# SoM.net
KiCad netlist of a schematic drawn in Altium Designer
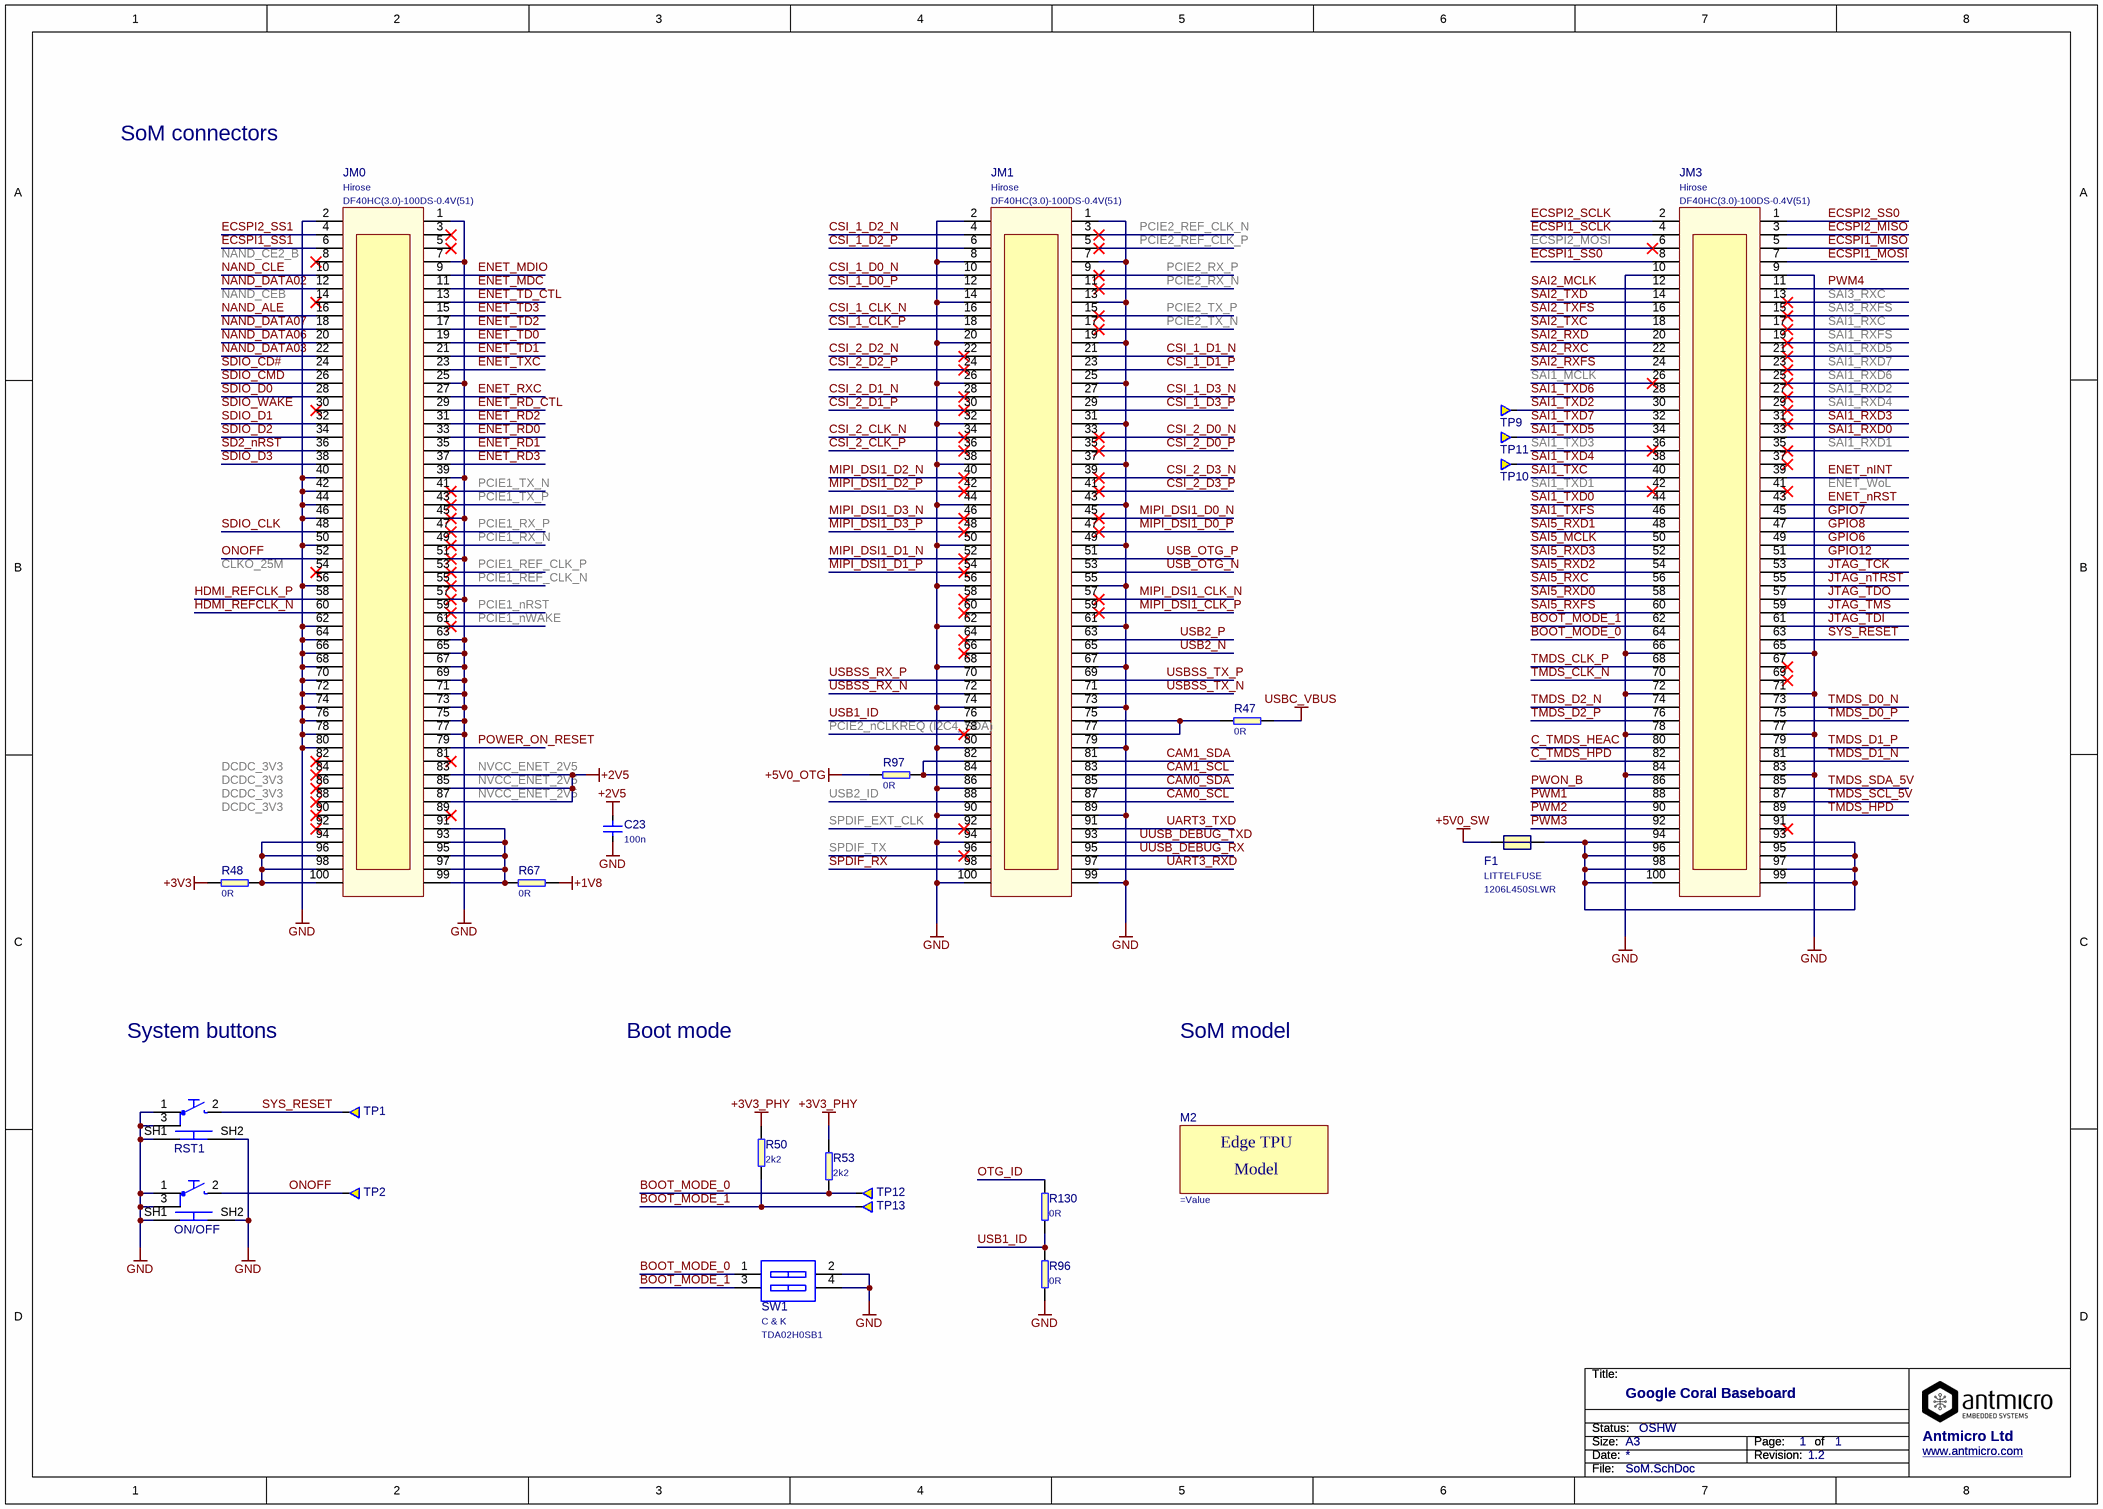
[diagram p0: SoM.SchDoc]

(export (version "E")
  (design (tool "Eeschema 10.0.6"))
  (components
    (comp (ref "C23")
      (value "100n")
      (footprint "C_0402")
      (description "MLCC SMT Capacitor 100nF 0402")
      (fields (field (name "PARTNUMBER") "C_100n_0402"))
      (libsource (lib "altium-import") (part "root_3_C_"))
    )
    (comp (ref "F1")
      (value "Value")
      (footprint "Fuse-1206")
      (description "PTC RESET 6V LO RHO 1206 4.50A")
      (fields (field (name "PARTNUMBER") "1206L450SLWR") (field (name "MANUFACTURER") "LITTELFUSE"))
      (libsource (lib "altium-import") (part "root_0_Fuse_"))
    )
    (comp (ref "JM0")
      (value "DF40HC(3.0)-100DS-0.4V(51)")
      (footprint "DF40HC(3.0)-100DS-0.4V(51)")
      (description "CONN RCPT 100POS 0.4MM SMD GOLD")
      (fields (field (name "MANUFACTURER") "Hirose"))
      (libsource (lib "altium-import") (part "root_0_DF40HC(3.0)-100DS-0.4V(51)_"))
    )
    (comp (ref "JM1")
      (value "DF40HC(3.0)-100DS-0.4V(51)")
      (footprint "DF40HC(3.0)-100DS-0.4V(51)")
      (description "CONN RCPT 100POS 0.4MM SMD GOLD")
      (fields (field (name "MANUFACTURER") "Hirose"))
      (libsource (lib "altium-import") (part "root_0_DF40HC(3.0)-100DS-0.4V(51)_"))
    )
    (comp (ref "JM3")
      (value "DF40HC(3.0)-100DS-0.4V(51)")
      (footprint "DF40HC(3.0)-100DS-0.4V(51)")
      (description "CONN RCPT 100POS 0.4MM SMD GOLD")
      (fields (field (name "MANUFACTURER") "Hirose"))
      (libsource (lib "altium-import") (part "root_0_DF40HC(3.0)-100DS-0.4V(51)_"))
    )
    (comp (ref "M2")
      (value "~")
      (footprint "Edge-TPU-SOM-model")
      (description "Edge TPU SOM")
      (fields (field (name "PARTNUMBER") "Edge-TPU-SOM-model"))
      (libsource (lib "altium-import") (part "root_0_Edge-TPU-Module-model_"))
    )
    (comp (ref "ON/OFF")
      (value "TL3340AF160QG")
      (footprint "TL3340AF160QG")
      (description "E-SWITCH  TL3340AF160QG  SWITCH, TACTILE SPST 50mA, SMD GULL WING")
      (fields (field (name "MANUFACTURER") "E-SWITCH"))
      (libsource (lib "altium-import") (part "root_0_TL3340AF160QG_"))
    )
    (comp (ref "R47")
      (value "0R")
      (footprint "0402")
      (description "SMT Resistor 0402")
      (fields (field (name "PARTNUMBER") "R_0R_0402"))
      (libsource (lib "altium-import") (part "root_2_R_"))
    )
    (comp (ref "R48")
      (value "0R")
      (footprint "0805")
      (description "SMT Resistor 0R 0805")
      (fields (field (name "PARTNUMBER") "R_0R_0805"))
      (libsource (lib "altium-import") (part "root_2_R_"))
    )
    (comp (ref "R50")
      (value "2k2")
      (footprint "0402")
      (description "RES, 2k2, 0402, 5%")
      (fields (field (name "PARTNUMBER") "R_2k2_0402"))
      (libsource (lib "altium-import") (part "root_1_R_"))
    )
    (comp (ref "R53")
      (value "2k2")
      (footprint "0402")
      (description "RES, 2k2, 0402, 5%")
      (fields (field (name "PARTNUMBER") "R_2k2_0402"))
      (libsource (lib "altium-import") (part "root_1_R_"))
    )
    (comp (ref "R67")
      (value "0R")
      (footprint "0805")
      (description "SMT Resistor 0R 0805")
      (fields (field (name "PARTNUMBER") "R_0R_0805"))
      (libsource (lib "altium-import") (part "root_0_R_"))
    )
    (comp (ref "R96")
      (value "0R")
      (footprint "0402")
      (description "SMT Resistor 0402")
      (fields (field (name "PARTNUMBER") "R_0R_0402"))
      (libsource (lib "altium-import") (part "root_1_R_"))
    )
    (comp (ref "R97")
      (value "0R")
      (footprint "0402")
      (description "SMT Resistor 0402")
      (fields (field (name "PARTNUMBER") "R_0R_0402"))
      (libsource (lib "altium-import") (part "root_2_R_"))
    )
    (comp (ref "R130")
      (value "0R")
      (footprint "0402")
      (description "SMT Resistor 0402")
      (fields (field (name "PARTNUMBER") "R_0R_0402"))
      (libsource (lib "altium-import") (part "root_1_R_"))
    )
    (comp (ref "RST1")
      (value "TL3340AF160QG")
      (footprint "TL3340AF160QG")
      (description "E-SWITCH  TL3340AF160QG  SWITCH, TACTILE SPST 50mA, SMD GULL WING")
      (fields (field (name "MANUFACTURER") "E-SWITCH"))
      (libsource (lib "altium-import") (part "root_0_TL3340AF160QG_"))
    )
    (comp (ref "SW1")
      (value "TDA02H0SB1")
      (footprint "TDA02H0SB1")
      (description "TDA02H0SB1 - DIP / SIP Switch, 2 Circuits, SPST, SMD, TDA Series, DIP, 24 V")
      (fields (field (name "MANUFACTURER") "C & K"))
      (libsource (lib "altium-import") (part "root_0_TDA02H0SB1_"))
    )
    (comp (ref "TP1")
      (value "Testpad")
      (footprint "TP-R-1.5")
      (description "Testpad, round, 1.5mm")
      (libsource (lib "altium-import") (part "root_3_Testpad_"))
    )
    (comp (ref "TP2")
      (value "Testpad")
      (footprint "TP-R-1.5")
      (description "Testpad, round, 1.5mm")
      (libsource (lib "altium-import") (part "root_3_Testpad_"))
    )
    (comp (ref "TP9")
      (value "Testpad")
      (footprint "TP-R-1.5")
      (description "Testpad, round, 1.5mm")
      (libsource (lib "altium-import") (part "root_1_Testpad_"))
    )
    (comp (ref "TP10")
      (value "Testpad")
      (footprint "TP-R-1.5")
      (description "Testpad, round, 1.5mm")
      (libsource (lib "altium-import") (part "root_1_Testpad_"))
    )
    (comp (ref "TP11")
      (value "Testpad")
      (footprint "TP-R-1.5")
      (description "Testpad, round, 1.5mm")
      (libsource (lib "altium-import") (part "root_1_Testpad_"))
    )
    (comp (ref "TP12")
      (value "Testpad")
      (footprint "TP-R-1.5")
      (description "Testpad, round, 1.5mm")
      (libsource (lib "altium-import") (part "root_3_Testpad_"))
    )
    (comp (ref "TP13")
      (value "Testpad")
      (footprint "TP-R-1.5")
      (description "Testpad, round, 1.5mm")
      (libsource (lib "altium-import") (part "root_3_Testpad_"))
    )
  )
  (nets
    (net (code "1") (name "+1V8") (class "Default") (node (ref "R67") (pin "2") (pintype "passive")))
    (net (code "2") (name "+2V5") (class "Default")
      (node (ref "C23") (pin "1") (pinfunction "1_1") (pintype "passive"))
      (node (ref "JM0") (pin "83") (pinfunction "PB8_83") (pintype "passive"))
      (node (ref "JM0") (pin "85") (pinfunction "PB8_85") (pintype "passive"))
      (node (ref "JM0") (pin "87") (pinfunction "PB8_87") (pintype "passive"))
    )
    (net (code "3") (name "+3V3") (class "Default") (node (ref "R48") (pin "2") (pintype "passive")))
    (net (code "4") (name "+3V3_PHY") (class "Default")
      (node (ref "R50") (pin "2") (pintype "passive"))
      (node (ref "R53") (pin "2") (pintype "passive"))
    )
    (net (code "5") (name "+5V0_OTG") (class "Default") (node (ref "R97") (pin "2") (pintype "passive")))
    (net (code "6") (name "+5V0_SW") (class "Default")
      (node (ref "F1") (pin "1") (pinfunction "1_1") (pintype "passive"))
    )
    (net (code "7") (name "/BOOT_MODE_0") (class "Default")
      (node (ref "JM3") (pin "64") (pinfunction "GND_64") (pintype "passive"))
      (node (ref "R53") (pin "1") (pintype "passive"))
      (node (ref "SW1") (pin "1") (pinfunction "1_1") (pintype "passive"))
      (node (ref "TP12") (pin "1") (pintype "passive"))
    )
    (net (code "8") (name "/BOOT_MODE_1") (class "Default")
      (node (ref "JM3") (pin "62") (pinfunction "PB12_62") (pintype "passive"))
      (node (ref "R50") (pin "1") (pintype "passive"))
      (node (ref "SW1") (pin "3") (pinfunction "3_3") (pintype "passive"))
      (node (ref "TP13") (pin "1") (pintype "passive"))
    )
    (net (code "9") (name "/CAM0_SCL") (class "Default")
      (node (ref "JM1") (pin "87") (pinfunction "PB8_87") (pintype "passive"))
    )
    (net (code "10") (name "/CAM0_SDA") (class "Default")
      (node (ref "JM1") (pin "85") (pinfunction "PB8_85") (pintype "passive"))
    )
    (net (code "11") (name "/CAM1_SCL") (class "Default")
      (node (ref "JM1") (pin "83") (pinfunction "PB8_83") (pintype "passive"))
    )
    (net (code "12") (name "/CAM1_SDA") (class "Default")
      (node (ref "JM1") (pin "81") (pinfunction "PB8_81") (pintype "passive"))
    )
    (net (code "14") (name "/CSI_1_CLK_N") (class "Default")
      (node (ref "JM1") (pin "16") (pinfunction "PE10_16") (pintype "passive"))
    )
    (net (code "15") (name "/CSI_1_CLK_P") (class "Default")
      (node (ref "JM1") (pin "18") (pinfunction "PE9_18") (pintype "passive"))
    )
    (net (code "16") (name "/CSI_1_D0_N") (class "Default")
      (node (ref "JM1") (pin "10") (pinfunction "PB15_10") (pintype "passive"))
    )
    (net (code "17") (name "/CSI_1_D0_P") (class "Default")
      (node (ref "JM1") (pin "12") (pinfunction "PB14_12") (pintype "passive"))
    )
    (net (code "18") (name "/CSI_1_D1_N") (class "Default")
      (node (ref "JM1") (pin "21") (pinfunction "1V8_21") (pintype "passive"))
    )
    (net (code "19") (name "/CSI_1_D1_P") (class "Default")
      (node (ref "JM1") (pin "23") (pinfunction "PE7_23") (pintype "passive"))
    )
    (net (code "20") (name "/CSI_1_D2_N") (class "Default")
      (node (ref "JM1") (pin "4") (pinfunction "2_4") (pintype "passive"))
    )
    (net (code "21") (name "/CSI_1_D2_P") (class "Default")
      (node (ref "JM1") (pin "6") (pinfunction "3_6") (pintype "passive"))
    )
    (net (code "22") (name "/CSI_1_D3_N") (class "Default")
      (node (ref "JM1") (pin "27") (pinfunction "PD1_27") (pintype "passive"))
    )
    (net (code "23") (name "/CSI_1_D3_P") (class "Default")
      (node (ref "JM1") (pin "29") (pinfunction "PD0_29") (pintype "passive"))
    )
    (net (code "24") (name "/CSI_2_CLK_N") (class "Default")
      (node (ref "JM1") (pin "34") (pinfunction "PC10_34") (pintype "passive+no_connect"))
    )
    (net (code "25") (name "/CSI_2_CLK_P") (class "Default")
      (node (ref "JM1") (pin "36") (pinfunction "PA15_36") (pintype "passive+no_connect"))
    )
    (net (code "26") (name "/CSI_2_D0_N") (class "Default")
      (node (ref "JM1") (pin "33") (pinfunction "PD4_33") (pintype "passive+no_connect"))
    )
    (net (code "27") (name "/CSI_2_D0_P") (class "Default")
      (node (ref "JM1") (pin "35") (pinfunction "PD7_35") (pintype "passive+no_connect"))
    )
    (net (code "28") (name "/CSI_2_D1_N") (class "Default")
      (node (ref "JM1") (pin "28") (pinfunction "GND_28") (pintype "passive+no_connect"))
    )
    (net (code "29") (name "/CSI_2_D1_P") (class "Default")
      (node (ref "JM1") (pin "30") (pinfunction "PA9_30") (pintype "passive+no_connect"))
    )
    (net (code "30") (name "/CSI_2_D2_N") (class "Default")
      (node (ref "JM1") (pin "22") (pinfunction "PD15_22") (pintype "passive+no_connect"))
    )
    (net (code "31") (name "/CSI_2_D2_P") (class "Default")
      (node (ref "JM1") (pin "24") (pinfunction "PC6_24") (pintype "passive+no_connect"))
    )
    (net (code "32") (name "/CSI_2_D3_N") (class "Default")
      (node (ref "JM1") (pin "39") (pinfunction "GND_39") (pintype "passive+no_connect"))
    )
    (net (code "33") (name "/CSI_2_D3_P") (class "Default")
      (node (ref "JM1") (pin "41") (pinfunction "RST_JTAG_O_41") (pintype "passive+no_connect"))
    )
    (net (code "34") (name "/C_TMDS_HEAC") (class "Default")
      (node (ref "JM3") (pin "80") (pinfunction "ETH_R_N_80") (pintype "passive"))
    )
    (net (code "35") (name "/C_TMDS_HPD") (class "Default")
      (node (ref "JM3") (pin "82") (pinfunction "PB8_82") (pintype "passive"))
    )
    (net (code "37") (name "/ECSPI1_MISO") (class "Default")
      (node (ref "JM3") (pin "5") (pinfunction "ETH_T_P_5") (pintype "passive"))
    )
    (net (code "38") (name "/ECSPI1_MOSI") (class "Default")
      (node (ref "JM3") (pin "7") (pinfunction "ETH_L1_C_7") (pintype "passive"))
    )
    (net (code "39") (name "/ECSPI1_SCLK") (class "Default")
      (node (ref "JM3") (pin "4") (pinfunction "2_4") (pintype "passive"))
    )
    (net (code "40") (name "/ECSPI1_SS0") (class "Default")
      (node (ref "JM3") (pin "8") (pinfunction "GND_8") (pintype "passive"))
    )
    (net (code "41") (name "/ECSPI1_SS1") (class "Default")
      (node (ref "JM0") (pin "6") (pinfunction "3_6") (pintype "passive"))
    )
    (net (code "42") (name "/ECSPI2_MISO") (class "Default")
      (node (ref "JM3") (pin "3") (pinfunction "ETH_T_N_3") (pintype "passive"))
    )
    (net (code "43") (name "/ECSPI2_MOSI") (class "Default")
      (node (ref "JM3") (pin "6") (pinfunction "3_6") (pintype "passive+no_connect"))
    )
    (net (code "44") (name "/ECSPI2_SCLK") (class "Default")
      (node (ref "JM3") (pin "2") (pinfunction "1_2") (pintype "passive"))
    )
    (net (code "45") (name "/ECSPI2_SS0") (class "Default")
      (node (ref "JM3") (pin "1") (pinfunction "ETH_VDD_1") (pintype "passive"))
    )
    (net (code "46") (name "/ECSPI2_SS1") (class "Default")
      (node (ref "JM0") (pin "4") (pinfunction "2_4") (pintype "passive"))
    )
    (net (code "47") (name "/ENET_MDC") (class "Default")
      (node (ref "JM0") (pin "11") (pinfunction "BATT_P_11") (pintype "passive"))
    )
    (net (code "48") (name "/ENET_MDIO") (class "Default")
      (node (ref "JM0") (pin "9") (pinfunction "GND_9") (pintype "passive"))
    )
    (net (code "49") (name "/ENET_RD0") (class "Default")
      (node (ref "JM0") (pin "33") (pinfunction "PD4_33") (pintype "passive"))
    )
    (net (code "50") (name "/ENET_RD1") (class "Default")
      (node (ref "JM0") (pin "35") (pinfunction "PD7_35") (pintype "passive"))
    )
    (net (code "51") (name "/ENET_RD2") (class "Default")
      (node (ref "JM0") (pin "31") (pinfunction "PD5_31") (pintype "passive"))
    )
    (net (code "52") (name "/ENET_RD3") (class "Default")
      (node (ref "JM0") (pin "37") (pinfunction "PF0_37") (pintype "passive"))
    )
    (net (code "53") (name "/ENET_RD_CTL") (class "Default")
      (node (ref "JM0") (pin "29") (pinfunction "PD0_29") (pintype "passive"))
    )
    (net (code "54") (name "/ENET_RXC") (class "Default")
      (node (ref "JM0") (pin "27") (pinfunction "PD1_27") (pintype "passive"))
    )
    (net (code "55") (name "/ENET_TD0") (class "Default")
      (node (ref "JM0") (pin "19") (pinfunction "CHRG_NTC_19") (pintype "passive"))
    )
    (net (code "56") (name "/ENET_TD1") (class "Default")
      (node (ref "JM0") (pin "21") (pinfunction "1V8_21") (pintype "passive"))
    )
    (net (code "57") (name "/ENET_TD2") (class "Default")
      (node (ref "JM0") (pin "17") (pinfunction "USB_VBUS_17") (pintype "passive"))
    )
    (net (code "58") (name "/ENET_TD3") (class "Default")
      (node (ref "JM0") (pin "15") (pinfunction "USB_VBUS_15") (pintype "passive"))
    )
    (net (code "59") (name "/ENET_TD_CTL") (class "Default")
      (node (ref "JM0") (pin "13") (pinfunction "BATT_P_13") (pintype "passive"))
    )
    (net (code "60") (name "/ENET_TXC") (class "Default")
      (node (ref "JM0") (pin "23") (pinfunction "PE7_23") (pintype "passive"))
    )
    (net (code "62") (name "/ENET_nINT") (class "Default")
      (node (ref "JM3") (pin "39") (pinfunction "GND_39") (pintype "passive"))
    )
    (net (code "63") (name "/ENET_nRST") (class "Default")
      (node (ref "JM3") (pin "43") (pinfunction "PB3_43") (pintype "passive"))
    )
    (net (code "64") (name "/GPIO6") (class "Default")
      (node (ref "JM3") (pin "49") (pinfunction "PI2_49") (pintype "passive"))
    )
    (net (code "65") (name "/GPIO7") (class "Default")
      (node (ref "JM3") (pin "45") (pinfunction "PA14_45") (pintype "passive"))
    )
    (net (code "66") (name "/GPIO8") (class "Default")
      (node (ref "JM3") (pin "47") (pinfunction "PA13_47") (pintype "passive"))
    )
    (net (code "67") (name "/GPIO12") (class "Default")
      (node (ref "JM3") (pin "51") (pinfunction "PI3_51") (pintype "passive"))
    )
    (net (code "68") (name "/HDMI_REFCLK_N") (class "Default")
      (node (ref "JM0") (pin "60") (pinfunction "PI1_60") (pintype "passive"))
    )
    (net (code "69") (name "/HDMI_REFCLK_P") (class "Default")
      (node (ref "JM0") (pin "58") (pinfunction "PB5_58") (pintype "passive"))
    )
    (net (code "70") (name "/JTAG_TCK") (class "Default")
      (node (ref "JM3") (pin "53") (pinfunction "PA12_53") (pintype "passive"))
    )
    (net (code "71") (name "/JTAG_TDI") (class "Default")
      (node (ref "JM3") (pin "61") (pinfunction "PC7_61") (pintype "passive"))
    )
    (net (code "72") (name "/JTAG_TDO") (class "Default")
      (node (ref "JM3") (pin "57") (pinfunction "PI0_57") (pintype "passive"))
    )
    (net (code "73") (name "/JTAG_TMS") (class "Default")
      (node (ref "JM3") (pin "59") (pinfunction "PD6_59") (pintype "passive"))
    )
    (net (code "74") (name "/JTAG_nTRST") (class "Default")
      (node (ref "JM3") (pin "55") (pinfunction "PA11_55") (pintype "passive"))
    )
    (net (code "75") (name "/MIPI_DSI1_CLK_N") (class "Default")
      (node (ref "JM1") (pin "57") (pinfunction "PI0_57") (pintype "passive+no_connect"))
    )
    (net (code "76") (name "/MIPI_DSI1_CLK_P") (class "Default")
      (node (ref "JM1") (pin "59") (pinfunction "PD6_59") (pintype "passive+no_connect"))
    )
    (net (code "77") (name "/MIPI_DSI1_D0_N") (class "Default")
      (node (ref "JM1") (pin "45") (pinfunction "PA14_45") (pintype "passive+no_connect"))
    )
    (net (code "78") (name "/MIPI_DSI1_D0_P") (class "Default")
      (node (ref "JM1") (pin "47") (pinfunction "PA13_47") (pintype "passive+no_connect"))
    )
    (net (code "79") (name "/MIPI_DSI1_D1_N") (class "Default")
      (node (ref "JM1") (pin "52") (pinfunction "PC8_52") (pintype "passive+no_connect"))
    )
    (net (code "80") (name "/MIPI_DSI1_D1_P") (class "Default")
      (node (ref "JM1") (pin "54") (pinfunction "PB6_54") (pintype "passive+no_connect"))
    )
    (net (code "81") (name "/MIPI_DSI1_D2_N") (class "Default")
      (node (ref "JM1") (pin "40") (pinfunction "PC12_40") (pintype "passive+no_connect"))
    )
    (net (code "82") (name "/MIPI_DSI1_D2_P") (class "Default")
      (node (ref "JM1") (pin "42") (pinfunction "PB10_42") (pintype "passive+no_connect"))
    )
    (net (code "83") (name "/MIPI_DSI1_D3_N") (class "Default")
      (node (ref "JM1") (pin "46") (pinfunction "PG9_46") (pintype "passive+no_connect"))
    )
    (net (code "84") (name "/MIPI_DSI1_D3_P") (class "Default")
      (node (ref "JM1") (pin "48") (pinfunction "GND_48") (pintype "passive+no_connect"))
    )
    (net (code "85") (name "/NAND_ALE") (class "Default")
      (node (ref "JM0") (pin "16") (pinfunction "PE10_16") (pintype "passive"))
    )
    (net (code "88") (name "/NAND_CLE") (class "Default")
      (node (ref "JM0") (pin "10") (pinfunction "PB15_10") (pintype "passive"))
    )
    (net (code "89") (name "/NAND_DATA02") (class "Default")
      (node (ref "JM0") (pin "12") (pinfunction "PB14_12") (pintype "passive"))
    )
    (net (code "90") (name "/NAND_DATA03") (class "Default")
      (node (ref "JM0") (pin "22") (pinfunction "PD15_22") (pintype "passive"))
    )
    (net (code "91") (name "/NAND_DATA06") (class "Default")
      (node (ref "JM0") (pin "20") (pinfunction "PD14_20") (pintype "passive"))
    )
    (net (code "92") (name "/NAND_DATA07") (class "Default")
      (node (ref "JM0") (pin "18") (pinfunction "PE9_18") (pintype "passive"))
    )
    (net (code "93") (name "/ONOFF") (class "Default")
      (node (ref "JM0") (pin "52") (pinfunction "PC8_52") (pintype "passive"))
      (node (ref "ON/OFF") (pin "2") (pinfunction "2_2") (pintype "passive"))
      (node (ref "TP2") (pin "1") (pintype "passive"))
    )
    (net (code "94") (name "/OTG_ID") (class "Default") (node (ref "R130") (pin "2") (pintype "passive")))
    (net (code "95") (name "/PCIE1_REF_CLK_N") (class "Default")
      (node (ref "JM0") (pin "55") (pinfunction "PA11_55") (pintype "passive+no_connect"))
    )
    (net (code "96") (name "/PCIE1_REF_CLK_P") (class "Default")
      (node (ref "JM0") (pin "53") (pinfunction "PA12_53") (pintype "passive+no_connect"))
    )
    (net (code "97") (name "/PCIE1_RX_N") (class "Default")
      (node (ref "JM0") (pin "49") (pinfunction "PI2_49") (pintype "passive+no_connect"))
    )
    (net (code "98") (name "/PCIE1_RX_P") (class "Default")
      (node (ref "JM0") (pin "47") (pinfunction "PA13_47") (pintype "passive+no_connect"))
    )
    (net (code "99") (name "/PCIE1_TX_N") (class "Default")
      (node (ref "JM0") (pin "41") (pinfunction "RST_JTAG_O_41") (pintype "passive+no_connect"))
    )
    (net (code "100") (name "/PCIE1_TX_P") (class "Default")
      (node (ref "JM0") (pin "43") (pinfunction "PB3_43") (pintype "passive+no_connect"))
    )
    (net (code "101") (name "/PCIE1_nRST") (class "Default")
      (node (ref "JM0") (pin "59") (pinfunction "PD6_59") (pintype "passive+no_connect"))
    )
    (net (code "102") (name "/PCIE1_nWAKE") (class "Default")
      (node (ref "JM0") (pin "61") (pinfunction "PC7_61") (pintype "passive+no_connect"))
    )
    (net (code "103") (name "/PCIE2_REF_CLK_N") (class "Default")
      (node (ref "JM1") (pin "3") (pinfunction "ETH_T_N_3") (pintype "passive+no_connect"))
    )
    (net (code "104") (name "/PCIE2_REF_CLK_P") (class "Default")
      (node (ref "JM1") (pin "5") (pinfunction "ETH_T_P_5") (pintype "passive+no_connect"))
    )
    (net (code "105") (name "/PCIE2_RX_N") (class "Default")
      (node (ref "JM1") (pin "11") (pinfunction "BATT_P_11") (pintype "passive+no_connect"))
    )
    (net (code "106") (name "/PCIE2_RX_P") (class "Default")
      (node (ref "JM1") (pin "9") (pinfunction "GND_9") (pintype "passive+no_connect"))
    )
    (net (code "107") (name "/PCIE2_TX_N") (class "Default")
      (node (ref "JM1") (pin "17") (pinfunction "USB_VBUS_17") (pintype "passive+no_connect"))
    )
    (net (code "108") (name "/PCIE2_TX_P") (class "Default")
      (node (ref "JM1") (pin "15") (pinfunction "USB_VBUS_15") (pintype "passive+no_connect"))
    )
    (net (code "109") (name "/PCIE2_nCLKREQ (I2C4_SDA)") (class "Default")
      (node (ref "JM1") (pin "78") (pinfunction "PI6_78") (pintype "passive+no_connect"))
    )
    (net (code "110") (name "/POWER_ON_RESET") (class "Default")
      (node (ref "JM0") (pin "79") (pinfunction "PB8_79") (pintype "passive"))
    )
    (net (code "111") (name "/PWM1") (class "Default")
      (node (ref "JM3") (pin "88") (pinfunction "PB8_88") (pintype "passive"))
    )
    (net (code "112") (name "/PWM2") (class "Default")
      (node (ref "JM3") (pin "90") (pinfunction "PB8_90") (pintype "passive"))
    )
    (net (code "113") (name "/PWM3") (class "Default")
      (node (ref "JM3") (pin "92") (pinfunction "PB8_92") (pintype "passive"))
    )
    (net (code "114") (name "/PWM4") (class "Default")
      (node (ref "JM3") (pin "11") (pinfunction "BATT_P_11") (pintype "passive"))
    )
    (net (code "115") (name "/PWON_B") (class "Default")
      (node (ref "JM3") (pin "86") (pinfunction "PB8_86") (pintype "passive"))
    )
    (net (code "116") (name "/SAI1_MCLK") (class "Default")
      (node (ref "JM3") (pin "26") (pinfunction "PA8_26") (pintype "passive+no_connect"))
    )
    (net (code "117") (name "/SAI1_RXC") (class "Default")
      (node (ref "JM3") (pin "17") (pinfunction "USB_VBUS_17") (pintype "passive+no_connect"))
    )
    (net (code "118") (name "/SAI1_RXD0") (class "Default")
      (node (ref "JM3") (pin "33") (pinfunction "PD4_33") (pintype "passive"))
    )
    (net (code "119") (name "/SAI1_RXD1") (class "Default")
      (node (ref "JM3") (pin "35") (pinfunction "PD7_35") (pintype "passive+no_connect"))
    )
    (net (code "120") (name "/SAI1_RXD2") (class "Default")
      (node (ref "JM3") (pin "27") (pinfunction "PD1_27") (pintype "passive+no_connect"))
    )
    (net (code "121") (name "/SAI1_RXD3") (class "Default")
      (node (ref "JM3") (pin "31") (pinfunction "PD5_31") (pintype "passive+no_connect"))
    )
    (net (code "122") (name "/SAI1_RXD4") (class "Default")
      (node (ref "JM3") (pin "29") (pinfunction "PD0_29") (pintype "passive+no_connect"))
    )
    (net (code "123") (name "/SAI1_RXD5") (class "Default")
      (node (ref "JM3") (pin "21") (pinfunction "1V8_21") (pintype "passive+no_connect"))
    )
    (net (code "124") (name "/SAI1_RXD6") (class "Default")
      (node (ref "JM3") (pin "25") (pinfunction "PE8_25") (pintype "passive+no_connect"))
    )
    (net (code "125") (name "/SAI1_RXD7") (class "Default")
      (node (ref "JM3") (pin "23") (pinfunction "PE7_23") (pintype "passive+no_connect"))
    )
    (net (code "126") (name "/SAI1_RXFS") (class "Default")
      (node (ref "JM3") (pin "19") (pinfunction "CHRG_NTC_19") (pintype "passive+no_connect"))
    )
    (net (code "127") (name "/SAI1_TXC") (class "Default")
      (node (ref "JM3") (pin "40") (pinfunction "PC12_40") (pintype "passive"))
    )
    (net (code "128") (name "/SAI1_TXD0") (class "Default")
      (node (ref "JM3") (pin "44") (pinfunction "PB4_44") (pintype "passive"))
    )
    (net (code "129") (name "/SAI1_TXD1") (class "Default")
      (node (ref "JM3") (pin "42") (pinfunction "PB10_42") (pintype "passive+no_connect"))
    )
    (net (code "130") (name "/SAI1_TXD2") (class "Default")
      (node (ref "JM3") (pin "30") (pinfunction "PA9_30") (pintype "passive"))
      (node (ref "TP9") (pin "1") (pintype "passive"))
    )
    (net (code "131") (name "/SAI1_TXD3") (class "Default")
      (node (ref "JM3") (pin "36") (pinfunction "PA15_36") (pintype "passive+no_connect"))
    )
    (net (code "132") (name "/SAI1_TXD4") (class "Default")
      (node (ref "JM3") (pin "38") (pinfunction "PC11_38") (pintype "passive"))
      (node (ref "TP10") (pin "1") (pintype "passive"))
    )
    (net (code "133") (name "/SAI1_TXD5") (class "Default")
      (node (ref "JM3") (pin "34") (pinfunction "PC10_34") (pintype "passive"))
      (node (ref "TP11") (pin "1") (pintype "passive"))
    )
    (net (code "134") (name "/SAI1_TXD6") (class "Default")
      (node (ref "JM3") (pin "28") (pinfunction "GND_28") (pintype "passive"))
    )
    (net (code "135") (name "/SAI1_TXD7") (class "Default")
      (node (ref "JM3") (pin "32") (pinfunction "PA10_32") (pintype "passive"))
    )
    (net (code "136") (name "/SAI1_TXFS") (class "Default")
      (node (ref "JM3") (pin "46") (pinfunction "PG9_46") (pintype "passive"))
    )
    (net (code "137") (name "/SAI2_MCLK") (class "Default")
      (node (ref "JM3") (pin "12") (pinfunction "PB14_12") (pintype "passive"))
    )
    (net (code "138") (name "/SAI2_RXC") (class "Default")
      (node (ref "JM3") (pin "22") (pinfunction "PD15_22") (pintype "passive"))
    )
    (net (code "139") (name "/SAI2_RXD") (class "Default")
      (node (ref "JM3") (pin "20") (pinfunction "PD14_20") (pintype "passive"))
    )
    (net (code "140") (name "/SAI2_RXFS") (class "Default")
      (node (ref "JM3") (pin "24") (pinfunction "PC6_24") (pintype "passive"))
    )
    (net (code "141") (name "/SAI2_TXC") (class "Default")
      (node (ref "JM3") (pin "18") (pinfunction "PE9_18") (pintype "passive"))
    )
    (net (code "142") (name "/SAI2_TXD") (class "Default")
      (node (ref "JM3") (pin "14") (pinfunction "NRST_14") (pintype "passive"))
    )
    (net (code "143") (name "/SAI2_TXFS") (class "Default")
      (node (ref "JM3") (pin "16") (pinfunction "PE10_16") (pintype "passive"))
    )
    (net (code "144") (name "/SAI3_RXC") (class "Default")
      (node (ref "JM3") (pin "13") (pinfunction "BATT_P_13") (pintype "passive+no_connect"))
    )
    (net (code "145") (name "/SAI3_RXFS") (class "Default")
      (node (ref "JM3") (pin "15") (pinfunction "USB_VBUS_15") (pintype "passive+no_connect"))
    )
    (net (code "146") (name "/SAI5_MCLK") (class "Default")
      (node (ref "JM3") (pin "50") (pinfunction "BOOT0_50") (pintype "passive"))
    )
    (net (code "147") (name "/SAI5_RXC") (class "Default")
      (node (ref "JM3") (pin "56") (pinfunction "PB7_56") (pintype "passive"))
    )
    (net (code "148") (name "/SAI5_RXD0") (class "Default")
      (node (ref "JM3") (pin "58") (pinfunction "PB5_58") (pintype "passive"))
    )
    (net (code "149") (name "/SAI5_RXD1") (class "Default")
      (node (ref "JM3") (pin "48") (pinfunction "GND_48") (pintype "passive"))
    )
    (net (code "150") (name "/SAI5_RXD2") (class "Default")
      (node (ref "JM3") (pin "54") (pinfunction "PB6_54") (pintype "passive"))
    )
    (net (code "151") (name "/SAI5_RXD3") (class "Default")
      (node (ref "JM3") (pin "52") (pinfunction "PC8_52") (pintype "passive"))
    )
    (net (code "152") (name "/SAI5_RXFS") (class "Default")
      (node (ref "JM3") (pin "60") (pinfunction "PI1_60") (pintype "passive"))
    )
    (net (code "153") (name "/SD2_nRST") (class "Default")
      (node (ref "JM0") (pin "36") (pinfunction "PA15_36") (pintype "passive"))
    )
    (net (code "154") (name "/SDIO_CD#") (class "Default")
      (node (ref "JM0") (pin "24") (pinfunction "PC6_24") (pintype "passive"))
    )
    (net (code "155") (name "/SDIO_CLK") (class "Default")
      (node (ref "JM0") (pin "48") (pinfunction "GND_48") (pintype "passive"))
    )
    (net (code "156") (name "/SDIO_CMD") (class "Default")
      (node (ref "JM0") (pin "26") (pinfunction "PA8_26") (pintype "passive"))
    )
    (net (code "157") (name "/SDIO_D0") (class "Default")
      (node (ref "JM0") (pin "28") (pinfunction "GND_28") (pintype "passive"))
    )
    (net (code "158") (name "/SDIO_D1") (class "Default")
      (node (ref "JM0") (pin "32") (pinfunction "PA10_32") (pintype "passive"))
    )
    (net (code "159") (name "/SDIO_D2") (class "Default")
      (node (ref "JM0") (pin "34") (pinfunction "PC10_34") (pintype "passive"))
    )
    (net (code "160") (name "/SDIO_D3") (class "Default")
      (node (ref "JM0") (pin "38") (pinfunction "PC11_38") (pintype "passive"))
    )
    (net (code "162") (name "/SPDIF_EXT_CLK") (class "Default")
      (node (ref "JM1") (pin "92") (pinfunction "PB8_92") (pintype "passive+no_connect"))
    )
    (net (code "163") (name "/SPDIF_RX") (class "Default")
      (node (ref "JM1") (pin "98") (pinfunction "PB8_98") (pintype "passive"))
    )
    (net (code "164") (name "/SPDIF_TX") (class "Default")
      (node (ref "JM1") (pin "96") (pinfunction "PB8_96") (pintype "passive+no_connect"))
    )
    (net (code "165") (name "/SYS_RESET") (class "Default")
      (node (ref "JM3") (pin "63") (pinfunction "PG7_63") (pintype "passive"))
      (node (ref "RST1") (pin "2") (pinfunction "2_2") (pintype "passive"))
      (node (ref "TP1") (pin "1") (pintype "passive"))
    )
    (net (code "166") (name "/TMDS_CLK_N") (class "Default")
      (node (ref "JM3") (pin "70") (pinfunction "PH15_70") (pintype "passive"))
    )
    (net (code "167") (name "/TMDS_CLK_P") (class "Default")
      (node (ref "JM3") (pin "68") (pinfunction "PG11_68") (pintype "passive"))
    )
    (net (code "168") (name "/TMDS_D0_N") (class "Default")
      (node (ref "JM3") (pin "73") (pinfunction "PH13_73") (pintype "passive"))
    )
    (net (code "169") (name "/TMDS_D0_P") (class "Default")
      (node (ref "JM3") (pin "75") (pinfunction "PH9_75") (pintype "passive"))
    )
    (net (code "170") (name "/TMDS_D1_N") (class "Default")
      (node (ref "JM3") (pin "81") (pinfunction "PB8_81") (pintype "passive"))
    )
    (net (code "171") (name "/TMDS_D1_P") (class "Default")
      (node (ref "JM3") (pin "79") (pinfunction "PB8_79") (pintype "passive"))
    )
    (net (code "172") (name "/TMDS_D2_N") (class "Default")
      (node (ref "JM3") (pin "74") (pinfunction "PH8_74") (pintype "passive"))
    )
    (net (code "173") (name "/TMDS_D2_P") (class "Default")
      (node (ref "JM3") (pin "76") (pinfunction "PI5_76") (pintype "passive"))
    )
    (net (code "174") (name "/TMDS_HPD") (class "Default")
      (node (ref "JM3") (pin "89") (pinfunction "PB8_89") (pintype "passive"))
    )
    (net (code "175") (name "/TMDS_SCL_5V") (class "Default")
      (node (ref "JM3") (pin "87") (pinfunction "PB8_87") (pintype "passive"))
    )
    (net (code "176") (name "/TMDS_SDA_5V") (class "Default")
      (node (ref "JM3") (pin "85") (pinfunction "PB8_85") (pintype "passive"))
    )
    (net (code "177") (name "/UART3_RXD") (class "Default")
      (node (ref "JM1") (pin "97") (pinfunction "PB8_97") (pintype "passive"))
    )
    (net (code "178") (name "/UART3_TXD") (class "Default")
      (node (ref "JM1") (pin "91") (pinfunction "PB8_91") (pintype "passive"))
    )
    (net (code "179") (name "/USB1_ID") (class "Default")
      (node (ref "JM1") (pin "76") (pinfunction "PI5_76") (pintype "passive"))
      (node (ref "R130") (pin "1") (pintype "passive"))
      (node (ref "R96") (pin "2") (pintype "passive"))
    )
    (net (code "180") (name "/USB2_ID") (class "Default")
      (node (ref "JM1") (pin "88") (pinfunction "PB8_88") (pintype "passive"))
    )
    (net (code "181") (name "/USB2_N") (class "Default")
      (node (ref "JM1") (pin "65") (pinfunction "PG6_65") (pintype "passive"))
    )
    (net (code "182") (name "/USB2_P") (class "Default")
      (node (ref "JM1") (pin "63") (pinfunction "PG7_63") (pintype "passive"))
    )
    (net (code "183") (name "/USBSS_RX_N") (class "Default")
      (node (ref "JM1") (pin "72") (pinfunction "PH12_72") (pintype "passive"))
    )
    (net (code "184") (name "/USBSS_RX_P") (class "Default")
      (node (ref "JM1") (pin "70") (pinfunction "PH15_70") (pintype "passive"))
    )
    (net (code "185") (name "/USBSS_TX_N") (class "Default")
      (node (ref "JM1") (pin "71") (pinfunction "PG12_71") (pintype "passive"))
    )
    (net (code "186") (name "/USBSS_TX_P") (class "Default")
      (node (ref "JM1") (pin "69") (pinfunction "PG10_69") (pintype "passive"))
    )
    (net (code "187") (name "/USB_OTG_N") (class "Default")
      (node (ref "JM1") (pin "53") (pinfunction "PA12_53") (pintype "passive"))
    )
    (net (code "188") (name "/USB_OTG_P") (class "Default")
      (node (ref "JM1") (pin "51") (pinfunction "PI3_51") (pintype "passive"))
    )
    (net (code "189") (name "/UUSB_DEBUG_RX") (class "Default")
      (node (ref "JM1") (pin "95") (pinfunction "PB8_95") (pintype "passive"))
    )
    (net (code "190") (name "/UUSB_DEBUG_TXD") (class "Default")
      (node (ref "JM1") (pin "93") (pinfunction "PB8_93") (pintype "passive"))
    )
    (net (code "191") (name "GND") (class "Default")
      (node (ref "C23") (pin "2") (pinfunction "2_2") (pintype "passive"))
      (node (ref "JM0") (pin "1") (pinfunction "ETH_VDD_1") (pintype "passive"))
      (node (ref "JM0") (pin "2") (pinfunction "1_2") (pintype "passive"))
      (node (ref "JM0") (pin "25") (pinfunction "PE8_25") (pintype "passive"))
      (node (ref "JM0") (pin "39") (pinfunction "GND_39") (pintype "passive"))
      (node (ref "JM0") (pin "40") (pinfunction "PC12_40") (pintype "passive"))
      (node (ref "JM0") (pin "42") (pinfunction "PB10_42") (pintype "passive"))
      (node (ref "JM0") (pin "44") (pinfunction "PB4_44") (pintype "passive"))
      (node (ref "JM0") (pin "45") (pinfunction "PA14_45") (pintype "passive"))
      (node (ref "JM0") (pin "46") (pinfunction "PG9_46") (pintype "passive"))
      (node (ref "JM0") (pin "50") (pinfunction "BOOT0_50") (pintype "passive"))
      (node (ref "JM0") (pin "51") (pinfunction "PI3_51") (pintype "passive"))
      (node (ref "JM0") (pin "56") (pinfunction "PB7_56") (pintype "passive"))
      (node (ref "JM0") (pin "57") (pinfunction "PI0_57") (pintype "passive"))
      (node (ref "JM0") (pin "62") (pinfunction "PB12_62") (pintype "passive"))
      (node (ref "JM0") (pin "63") (pinfunction "PG7_63") (pintype "passive"))
      (node (ref "JM0") (pin "64") (pinfunction "GND_64") (pintype "passive"))
      (node (ref "JM0") (pin "65") (pinfunction "PG6_65") (pintype "passive"))
      (node (ref "JM0") (pin "66") (pinfunction "BOOT1_66") (pintype "passive"))
      (node (ref "JM0") (pin "67") (pinfunction "PD3_67") (pintype "passive"))
      (node (ref "JM0") (pin "68") (pinfunction "PG11_68") (pintype "passive"))
      (node (ref "JM0") (pin "69") (pinfunction "PG10_69") (pintype "passive"))
      (node (ref "JM0") (pin "7") (pinfunction "ETH_L1_C_7") (pintype "passive"))
      (node (ref "JM0") (pin "70") (pinfunction "PH15_70") (pintype "passive"))
      (node (ref "JM0") (pin "71") (pinfunction "PG12_71") (pintype "passive"))
      (node (ref "JM0") (pin "72") (pinfunction "PH12_72") (pintype "passive"))
      (node (ref "JM0") (pin "73") (pinfunction "PH13_73") (pintype "passive"))
      (node (ref "JM0") (pin "74") (pinfunction "PH8_74") (pintype "passive"))
      (node (ref "JM0") (pin "75") (pinfunction "PH9_75") (pintype "passive"))
      (node (ref "JM0") (pin "76") (pinfunction "PI5_76") (pintype "passive"))
      (node (ref "JM0") (pin "77") (pinfunction "GND_77") (pintype "passive"))
      (node (ref "JM0") (pin "78") (pinfunction "PI6_78") (pintype "passive"))
      (node (ref "JM0") (pin "80") (pinfunction "ETH_R_N_80") (pintype "passive"))
      (node (ref "JM1") (pin "1") (pinfunction "ETH_VDD_1") (pintype "passive"))
      (node (ref "JM1") (pin "100") (pinfunction "PB8_100") (pintype "passive"))
      (node (ref "JM1") (pin "13") (pinfunction "BATT_P_13") (pintype "passive"))
      (node (ref "JM1") (pin "14") (pinfunction "NRST_14") (pintype "passive"))
      (node (ref "JM1") (pin "19") (pinfunction "CHRG_NTC_19") (pintype "passive"))
      (node (ref "JM1") (pin "2") (pinfunction "1_2") (pintype "passive"))
      (node (ref "JM1") (pin "20") (pinfunction "PD14_20") (pintype "passive"))
      (node (ref "JM1") (pin "25") (pinfunction "PE8_25") (pintype "passive"))
      (node (ref "JM1") (pin "26") (pinfunction "PA8_26") (pintype "passive"))
      (node (ref "JM1") (pin "31") (pinfunction "PD5_31") (pintype "passive"))
      (node (ref "JM1") (pin "32") (pinfunction "PA10_32") (pintype "passive"))
      (node (ref "JM1") (pin "37") (pinfunction "PF0_37") (pintype "passive"))
      (node (ref "JM1") (pin "38") (pinfunction "PC11_38") (pintype "passive"))
      (node (ref "JM1") (pin "43") (pinfunction "PB3_43") (pintype "passive"))
      (node (ref "JM1") (pin "44") (pinfunction "PB4_44") (pintype "passive"))
      (node (ref "JM1") (pin "49") (pinfunction "PI2_49") (pintype "passive"))
      (node (ref "JM1") (pin "50") (pinfunction "BOOT0_50") (pintype "passive"))
      (node (ref "JM1") (pin "55") (pinfunction "PA11_55") (pintype "passive"))
      (node (ref "JM1") (pin "56") (pinfunction "PB7_56") (pintype "passive"))
      (node (ref "JM1") (pin "61") (pinfunction "PC7_61") (pintype "passive"))
      (node (ref "JM1") (pin "62") (pinfunction "PB12_62") (pintype "passive"))
      (node (ref "JM1") (pin "67") (pinfunction "PD3_67") (pintype "passive"))
      (node (ref "JM1") (pin "68") (pinfunction "PG11_68") (pintype "passive"))
      (node (ref "JM1") (pin "7") (pinfunction "ETH_L1_C_7") (pintype "passive"))
      (node (ref "JM1") (pin "73") (pinfunction "PH13_73") (pintype "passive"))
      (node (ref "JM1") (pin "74") (pinfunction "PH8_74") (pintype "passive"))
      (node (ref "JM1") (pin "79") (pinfunction "PB8_79") (pintype "passive"))
      (node (ref "JM1") (pin "8") (pinfunction "GND_8") (pintype "passive"))
      (node (ref "JM1") (pin "80") (pinfunction "ETH_R_N_80") (pintype "passive"))
      (node (ref "JM1") (pin "86") (pinfunction "PB8_86") (pintype "passive"))
      (node (ref "JM1") (pin "89") (pinfunction "PB8_89") (pintype "passive"))
      (node (ref "JM1") (pin "90") (pinfunction "PB8_90") (pintype "passive"))
      (node (ref "JM1") (pin "94") (pinfunction "PB8_94") (pintype "passive"))
      (node (ref "JM1") (pin "99") (pinfunction "PB8_99") (pintype "passive"))
      (node (ref "JM3") (pin "10") (pinfunction "PB15_10") (pintype "passive"))
      (node (ref "JM3") (pin "65") (pinfunction "PG6_65") (pintype "passive"))
      (node (ref "JM3") (pin "66") (pinfunction "BOOT1_66") (pintype "passive"))
      (node (ref "JM3") (pin "71") (pinfunction "PG12_71") (pintype "passive"))
      (node (ref "JM3") (pin "72") (pinfunction "PH12_72") (pintype "passive"))
      (node (ref "JM3") (pin "77") (pinfunction "GND_77") (pintype "passive"))
      (node (ref "JM3") (pin "78") (pinfunction "PI6_78") (pintype "passive"))
      (node (ref "JM3") (pin "83") (pinfunction "PB8_83") (pintype "passive"))
      (node (ref "JM3") (pin "84") (pinfunction "PB8_84") (pintype "passive"))
      (node (ref "JM3") (pin "9") (pinfunction "GND_9") (pintype "passive"))
      (node (ref "ON/OFF") (pin "1") (pinfunction "1_1") (pintype "passive"))
      (node (ref "ON/OFF") (pin "3") (pinfunction "3_3") (pintype "passive"))
      (node (ref "ON/OFF") (pin "SH1") (pinfunction "SH1_SH1") (pintype "passive"))
      (node (ref "ON/OFF") (pin "SH2") (pinfunction "SH2_SH2") (pintype "passive"))
      (node (ref "R96") (pin "1") (pintype "passive"))
      (node (ref "RST1") (pin "1") (pinfunction "1_1") (pintype "passive"))
      (node (ref "RST1") (pin "3") (pinfunction "3_3") (pintype "passive"))
      (node (ref "RST1") (pin "SH1") (pinfunction "SH1_SH1") (pintype "passive"))
      (node (ref "RST1") (pin "SH2") (pinfunction "SH2_SH2") (pintype "passive"))
      (node (ref "SW1") (pin "2") (pinfunction "2_2") (pintype "passive"))
      (node (ref "SW1") (pin "4") (pinfunction "4_4") (pintype "passive"))
    )
    (net (code "192") (name "Net-(F1-Pad2)") (class "Default")
      (node (ref "F1") (pin "2") (pinfunction "2_2") (pintype "passive"))
      (node (ref "JM3") (pin "100") (pinfunction "PB8_100") (pintype "passive"))
      (node (ref "JM3") (pin "93") (pinfunction "PB8_93") (pintype "passive"))
      (node (ref "JM3") (pin "94") (pinfunction "PB8_94") (pintype "passive"))
      (node (ref "JM3") (pin "95") (pinfunction "PB8_95") (pintype "passive"))
      (node (ref "JM3") (pin "96") (pinfunction "PB8_96") (pintype "passive"))
      (node (ref "JM3") (pin "97") (pinfunction "PB8_97") (pintype "passive"))
      (node (ref "JM3") (pin "98") (pinfunction "PB8_98") (pintype "passive"))
      (node (ref "JM3") (pin "99") (pinfunction "PB8_99") (pintype "passive"))
    )
    (net (code "193") (name "Net-(JM0-PB8-Pad91)") (class "Default")
      (node (ref "JM0") (pin "91") (pinfunction "PB8_91") (pintype "passive"))
      (node (ref "JM0") (pin "93") (pinfunction "PB8_93") (pintype "passive"))
      (node (ref "JM0") (pin "95") (pinfunction "PB8_95") (pintype "passive"))
      (node (ref "JM0") (pin "97") (pinfunction "PB8_97") (pintype "passive"))
      (node (ref "JM0") (pin "99") (pinfunction "PB8_99") (pintype "passive"))
      (node (ref "R67") (pin "1") (pintype "passive"))
    )
    (net (code "194") (name "Net-(JM0-PB8-Pad100)") (class "Default")
      (node (ref "JM0") (pin "100") (pinfunction "PB8_100") (pintype "passive"))
      (node (ref "JM0") (pin "94") (pinfunction "PB8_94") (pintype "passive"))
      (node (ref "JM0") (pin "96") (pinfunction "PB8_96") (pintype "passive"))
      (node (ref "JM0") (pin "98") (pinfunction "PB8_98") (pintype "passive"))
      (node (ref "R48") (pin "1") (pintype "passive"))
    )
    (net (code "195") (name "Net-(JM1-PB8-Pad82)") (class "Default")
      (node (ref "JM1") (pin "82") (pinfunction "PB8_82") (pintype "passive"))
      (node (ref "JM1") (pin "84") (pinfunction "PB8_84") (pintype "passive"))
      (node (ref "R97") (pin "1") (pintype "passive"))
    )
    (net (code "196") (name "Net-(JM1-PH9)") (class "Default")
      (node (ref "JM1") (pin "75") (pinfunction "PH9_75") (pintype "passive"))
      (node (ref "JM1") (pin "77") (pinfunction "GND_77") (pintype "passive"))
      (node (ref "R47") (pin "2") (pintype "passive"))
    )
    (net (code "197") (name "USBC_VBUS") (class "Default") (node (ref "R47") (pin "1") (pintype "passive")))
    (net (code "198") (name "unconnected-(JM0-ETH_T_N-Pad3)") (class "Default")
      (node (ref "JM0") (pin "3") (pinfunction "ETH_T_N_3") (pintype "passive+no_connect"))
    )
    (net (code "199") (name "unconnected-(JM0-ETH_T_P-Pad5)") (class "Default")
      (node (ref "JM0") (pin "5") (pinfunction "ETH_T_P_5") (pintype "passive+no_connect"))
    )
    (net (code "200") (name "unconnected-(JM0-GND-Pad8)") (class "Default")
      (node (ref "JM0") (pin "8") (pinfunction "GND_8") (pintype "passive+no_connect"))
    )
    (net (code "201") (name "unconnected-(JM0-NRST-Pad14)") (class "Default")
      (node (ref "JM0") (pin "14") (pinfunction "NRST_14") (pintype "passive+no_connect"))
    )
    (net (code "202") (name "unconnected-(JM0-PA9-Pad30)") (class "Default")
      (node (ref "JM0") (pin "30") (pinfunction "PA9_30") (pintype "passive+no_connect"))
    )
    (net (code "203") (name "unconnected-(JM0-PB6-Pad54)") (class "Default")
      (node (ref "JM0") (pin "54") (pinfunction "PB6_54") (pintype "passive+no_connect"))
    )
    (net (code "204") (name "unconnected-(JM0-PB8-Pad81)") (class "Default")
      (node (ref "JM0") (pin "81") (pinfunction "PB8_81") (pintype "passive+no_connect"))
    )
    (net (code "205") (name "unconnected-(JM0-PB8-Pad82)") (class "Default")
      (node (ref "JM0") (pin "82") (pinfunction "PB8_82") (pintype "passive+no_connect"))
    )
    (net (code "206") (name "unconnected-(JM0-PB8-Pad84)") (class "Default")
      (node (ref "JM0") (pin "84") (pinfunction "PB8_84") (pintype "passive+no_connect"))
    )
    (net (code "207") (name "unconnected-(JM0-PB8-Pad86)") (class "Default")
      (node (ref "JM0") (pin "86") (pinfunction "PB8_86") (pintype "passive+no_connect"))
    )
    (net (code "208") (name "unconnected-(JM0-PB8-Pad88)") (class "Default")
      (node (ref "JM0") (pin "88") (pinfunction "PB8_88") (pintype "passive+no_connect"))
    )
    (net (code "209") (name "unconnected-(JM0-PB8-Pad89)") (class "Default")
      (node (ref "JM0") (pin "89") (pinfunction "PB8_89") (pintype "passive+no_connect"))
    )
    (net (code "210") (name "unconnected-(JM0-PB8-Pad90)") (class "Default")
      (node (ref "JM0") (pin "90") (pinfunction "PB8_90") (pintype "passive+no_connect"))
    )
    (net (code "211") (name "unconnected-(JM0-PB8-Pad92)") (class "Default")
      (node (ref "JM0") (pin "92") (pinfunction "PB8_92") (pintype "passive+no_connect"))
    )
    (net (code "212") (name "unconnected-(JM1-BOOT1-Pad66)") (class "Default")
      (node (ref "JM1") (pin "66") (pinfunction "BOOT1_66") (pintype "passive+no_connect"))
    )
    (net (code "213") (name "unconnected-(JM1-GND-Pad64)") (class "Default")
      (node (ref "JM1") (pin "64") (pinfunction "GND_64") (pintype "passive+no_connect"))
    )
    (net (code "214") (name "unconnected-(JM1-PB5-Pad58)") (class "Default")
      (node (ref "JM1") (pin "58") (pinfunction "PB5_58") (pintype "passive+no_connect"))
    )
    (net (code "215") (name "unconnected-(JM1-PI1-Pad60)") (class "Default")
      (node (ref "JM1") (pin "60") (pinfunction "PI1_60") (pintype "passive+no_connect"))
    )
    (net (code "216") (name "unconnected-(JM3-PB8-Pad91)") (class "Default")
      (node (ref "JM3") (pin "91") (pinfunction "PB8_91") (pintype "passive+no_connect"))
    )
    (net (code "217") (name "unconnected-(JM3-PD3-Pad67)") (class "Default")
      (node (ref "JM3") (pin "67") (pinfunction "PD3_67") (pintype "passive+no_connect"))
    )
    (net (code "218") (name "unconnected-(JM3-PF0-Pad37)") (class "Default")
      (node (ref "JM3") (pin "37") (pinfunction "PF0_37") (pintype "passive+no_connect"))
    )
    (net (code "219") (name "unconnected-(JM3-PG10-Pad69)") (class "Default")
      (node (ref "JM3") (pin "69") (pinfunction "PG10_69") (pintype "passive+no_connect"))
    )
    (net (code "220") (name "unconnected-(JM3-RST_JTAG_O-Pad41)") (class "Default")
      (node (ref "JM3") (pin "41") (pinfunction "RST_JTAG_O_41") (pintype "passive+no_connect"))
    )
  )
)
